# Analog_Sensors.net
KiCad netlist of a schematic drawn in Altium Designer
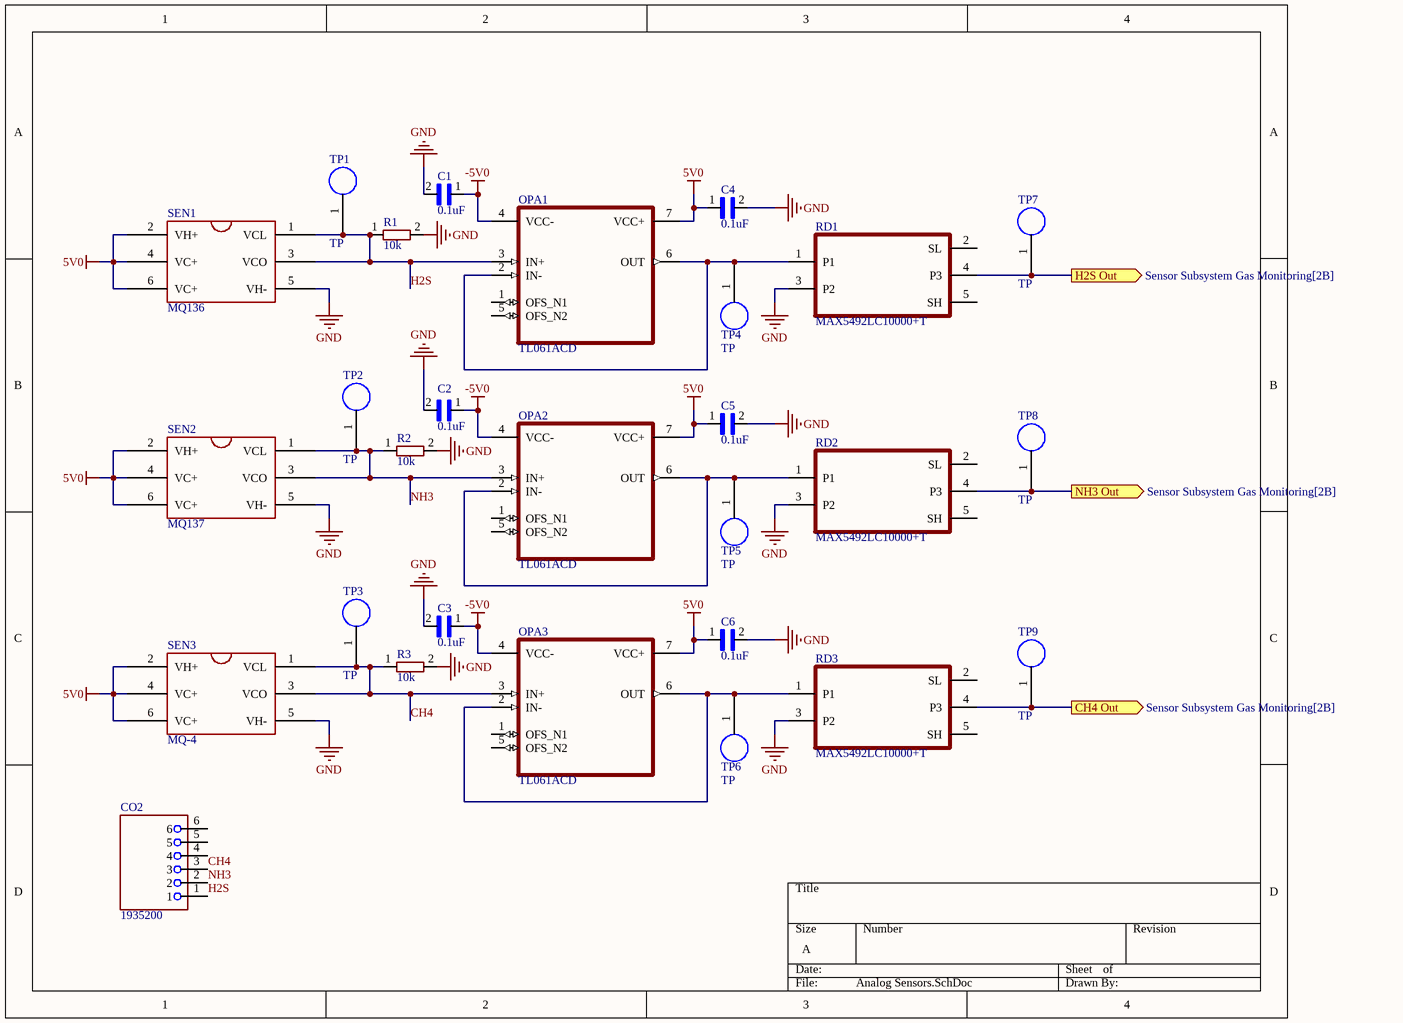
[diagram p0: Analog Sensors.SchDoc]

(export (version "E")
  (design (tool "Eeschema 10.0.6"))
  (components
    (comp (ref "C1")
      (value "0.1uF")
      (footprint "0.1uF Capacitor")
      (description "No Description Available")
      (libsource (lib "0.1uF Capacitor") (part "CC1206JRX7R9BB104"))
    )
    (comp (ref "C2")
      (value "0.1uF")
      (footprint "0.1uF Capacitor")
      (description "No Description Available")
      (libsource (lib "0.1uF Capacitor") (part "CC1206JRX7R9BB104"))
    )
    (comp (ref "C3")
      (value "0.1uF")
      (footprint "0.1uF Capacitor")
      (description "No Description Available")
      (libsource (lib "0.1uF Capacitor") (part "CC1206JRX7R9BB104"))
    )
    (comp (ref "C4")
      (value "0.1uF")
      (footprint "0.1uF Capacitor")
      (description "No Description Available")
      (libsource (lib "") (part "CC1206JRX7R9BB104_1"))
    )
    (comp (ref "C5")
      (value "0.1uF")
      (footprint "0.1uF Capacitor")
      (description "No Description Available")
      (libsource (lib "") (part "CC1206JRX7R9BB104_1"))
    )
    (comp (ref "C6")
      (value "0.1uF")
      (footprint "0.1uF Capacitor")
      (description "No Description Available")
      (libsource (lib "") (part "CC1206JRX7R9BB104_1"))
    )
    (comp (ref "CO2")
      (value "1935200")
      (footprint "PHOENIX_1935200")
      (fields (field (name "MF") "Littelfuse"))
      (libsource (lib "Main Connector") (part "1935200"))
    )
    (comp (ref "OPA1")
      (value "TL061ACD")
      (footprint "TL061ACD:SOIC127P599X175-8N")
      (libsource (lib "TL061ACD") (part "TL061ACD"))
    )
    (comp (ref "OPA2")
      (value "TL061ACD")
      (footprint "TL061ACD:SOIC127P599X175-8N")
      (libsource (lib "TL061ACD") (part "TL061ACD"))
    )
    (comp (ref "OPA3")
      (value "TL061ACD")
      (footprint "TL061ACD:SOIC127P599X175-8N")
      (libsource (lib "TL061ACD") (part "TL061ACD"))
    )
    (comp (ref "R1")
      (value "10k")
      (footprint "10K Resistor:0603")
      (description "http://octopart.com/rc0603fr-1310kl-yageo+%2F+phycomp-25905087")
      (fields (field (name "MP") "RC0603FR-1310KL"))
      (libsource (lib "10K Resistor") (part "RC0603FR-1310KL"))
    )
    (comp (ref "R2")
      (value "10k")
      (footprint "10K Resistor:0603")
      (description "http://octopart.com/rc0603fr-1310kl-yageo+%2F+phycomp-25905087")
      (fields (field (name "MP") "RC0603FR-1310KL"))
      (libsource (lib "10K Resistor") (part "RC0603FR-1310KL"))
    )
    (comp (ref "R3")
      (value "10k")
      (footprint "10K Resistor:0603")
      (description "http://octopart.com/rc0603fr-1310kl-yageo+%2F+phycomp-25905087")
      (fields (field (name "MP") "RC0603FR-1310KL"))
      (libsource (lib "10K Resistor") (part "RC0603FR-1310KL"))
    )
    (comp (ref "RD1")
      (value "MAX5492LC10000+T")
      (footprint "SOT95P280X145-5N")
      (description "Res NET 9.09K Ohm/910 Ohm 0.1% 0.5714W Â±35ppm/Â°C VOLT/D 5-Pin SOT-23 Gull Wing SMD T/R")
      (fields (field (name "MF") "Maxim Integrated Products"))
      (libsource (lib "Voltage Divider") (part "MAX5492LC10000+T"))
    )
    (comp (ref "RD2")
      (value "MAX5492LC10000+T")
      (footprint "SOT95P280X145-5N")
      (description "Res NET 9.09K Ohm/910 Ohm 0.1% 0.5714W Â±35ppm/Â°C VOLT/D 5-Pin SOT-23 Gull Wing SMD T/R")
      (fields (field (name "MF") "Maxim Integrated Products"))
      (libsource (lib "Voltage Divider") (part "MAX5492LC10000+T"))
    )
    (comp (ref "RD3")
      (value "MAX5492LC10000+T")
      (footprint "SOT95P280X145-5N")
      (description "Res NET 9.09K Ohm/910 Ohm 0.1% 0.5714W Â±35ppm/Â°C VOLT/D 5-Pin SOT-23 Gull Wing SMD T/R")
      (fields (field (name "MF") "Maxim Integrated Products"))
      (libsource (lib "Voltage Divider") (part "MAX5492LC10000+T"))
    )
    (comp (ref "SEN1")
      (value "MQ136")
      (footprint "MQ136")
      (description "Hydrogen Sulfide Sensor")
      (libsource (lib "MQ136") (part "MQ136"))
    )
    (comp (ref "SEN2")
      (value "MQ137")
      (footprint "MQ137")
      (description "Ammonia Sensor")
      (libsource (lib "MQ137") (part "MQ137"))
    )
    (comp (ref "SEN3")
      (value "MQ-4")
      (footprint "MQ4")
      (description "Methane Sensor")
      (libsource (lib "MQ-4") (part "MQ-4"))
    )
    (comp (ref "TP1")
      (value "TP")
      (footprint "TestPoint")
      (description "Test point for voltage, current, ect.")
      (libsource (lib "TestPoint") (part "TestPoint"))
    )
    (comp (ref "TP2")
      (value "TP")
      (footprint "TestPoint")
      (description "Test point for voltage, current, ect.")
      (libsource (lib "TestPoint") (part "TestPoint"))
    )
    (comp (ref "TP3")
      (value "TP")
      (footprint "TestPoint")
      (description "Test point for voltage, current, ect.")
      (libsource (lib "TestPoint") (part "TestPoint"))
    )
    (comp (ref "TP4")
      (value "TP")
      (footprint "TestPoint")
      (description "Test point for voltage, current, ect.")
      (libsource (lib "TestPoint") (part "TestPoint"))
    )
    (comp (ref "TP5")
      (value "TP")
      (footprint "TestPoint")
      (description "Test point for voltage, current, ect.")
      (libsource (lib "TestPoint") (part "TestPoint"))
    )
    (comp (ref "TP6")
      (value "TP")
      (footprint "TestPoint")
      (description "Test point for voltage, current, ect.")
      (libsource (lib "TestPoint") (part "TestPoint"))
    )
    (comp (ref "TP7")
      (value "TP")
      (footprint "TestPoint")
      (description "Test point for voltage, current, ect.")
      (libsource (lib "TestPoint") (part "TestPoint"))
    )
    (comp (ref "TP8")
      (value "TP")
      (footprint "TestPoint")
      (description "Test point for voltage, current, ect.")
      (libsource (lib "TestPoint") (part "TestPoint"))
    )
    (comp (ref "TP9")
      (value "TP")
      (footprint "TestPoint")
      (description "Test point for voltage, current, ect.")
      (libsource (lib "TestPoint") (part "TestPoint"))
    )
  )
  (nets
    (net (code "1") (name "-5V0") (class "Default")
      (node (ref "C1") (pin "1") (pintype "passive"))
      (node (ref "C2") (pin "1") (pintype "passive"))
      (node (ref "C3") (pin "1") (pintype "passive"))
      (node (ref "OPA1") (pin "4") (pinfunction "VCC-_4") (pintype "power_in"))
      (node (ref "OPA2") (pin "4") (pinfunction "VCC-_4") (pintype "power_in"))
      (node (ref "OPA3") (pin "4") (pinfunction "VCC-_4") (pintype "power_in"))
    )
    (net (code "2") (name "/CH4") (class "Default")
      (node (ref "CO2") (pin "3") (pinfunction "3_3") (pintype "passive"))
      (node (ref "OPA3") (pin "3") (pinfunction "IN+_3") (pintype "input"))
      (node (ref "R3") (pin "1") (pintype "passive"))
      (node (ref "SEN3") (pin "1") (pinfunction "VCL_1") (pintype "passive"))
      (node (ref "SEN3") (pin "3") (pinfunction "VCO_3") (pintype "passive"))
      (node (ref "TP3") (pin "1") (pintype "passive"))
    )
    (net (code "3") (name "/CH4 Out") (class "Default")
      (node (ref "RD3") (pin "4") (pinfunction "P3_4") (pintype "passive"))
      (node (ref "TP9") (pin "1") (pintype "passive"))
    )
    (net (code "4") (name "/H2S") (class "Default")
      (node (ref "CO2") (pin "1") (pinfunction "1_1") (pintype "passive"))
      (node (ref "OPA1") (pin "3") (pinfunction "IN+_3") (pintype "input"))
      (node (ref "R1") (pin "1") (pintype "passive"))
      (node (ref "SEN1") (pin "1") (pinfunction "VCL_1") (pintype "passive"))
      (node (ref "SEN1") (pin "3") (pinfunction "VCO_3") (pintype "passive"))
      (node (ref "TP1") (pin "1") (pintype "passive"))
    )
    (net (code "5") (name "/H2S Out") (class "Default")
      (node (ref "RD1") (pin "4") (pinfunction "P3_4") (pintype "passive"))
      (node (ref "TP7") (pin "1") (pintype "passive"))
    )
    (net (code "6") (name "/NH3") (class "Default")
      (node (ref "CO2") (pin "2") (pinfunction "2_2") (pintype "passive"))
      (node (ref "OPA2") (pin "3") (pinfunction "IN+_3") (pintype "input"))
      (node (ref "R2") (pin "1") (pintype "passive"))
      (node (ref "SEN2") (pin "1") (pinfunction "VCL_1") (pintype "passive"))
      (node (ref "SEN2") (pin "3") (pinfunction "VCO_3") (pintype "passive"))
      (node (ref "TP2") (pin "1") (pintype "passive"))
    )
    (net (code "7") (name "/NH3 Out") (class "Default")
      (node (ref "RD2") (pin "4") (pinfunction "P3_4") (pintype "passive"))
      (node (ref "TP8") (pin "1") (pintype "passive"))
    )
    (net (code "8") (name "5V0") (class "Default")
      (node (ref "C4") (pin "1") (pintype "passive"))
      (node (ref "C5") (pin "1") (pintype "passive"))
      (node (ref "C6") (pin "1") (pintype "passive"))
      (node (ref "OPA1") (pin "7") (pinfunction "VCC+_7") (pintype "power_in"))
      (node (ref "OPA2") (pin "7") (pinfunction "VCC+_7") (pintype "power_in"))
      (node (ref "OPA3") (pin "7") (pinfunction "VCC+_7") (pintype "power_in"))
      (node (ref "SEN1") (pin "2") (pinfunction "VH+_2") (pintype "passive"))
      (node (ref "SEN1") (pin "4") (pinfunction "VC+_4") (pintype "passive"))
      (node (ref "SEN1") (pin "6") (pinfunction "VC+_6") (pintype "passive"))
      (node (ref "SEN2") (pin "2") (pinfunction "VH+_2") (pintype "passive"))
      (node (ref "SEN2") (pin "4") (pinfunction "VC+_4") (pintype "passive"))
      (node (ref "SEN2") (pin "6") (pinfunction "VC+_6") (pintype "passive"))
      (node (ref "SEN3") (pin "2") (pinfunction "VH+_2") (pintype "passive"))
      (node (ref "SEN3") (pin "4") (pinfunction "VC+_4") (pintype "passive"))
      (node (ref "SEN3") (pin "6") (pinfunction "VC+_6") (pintype "passive"))
    )
    (net (code "9") (name "GND") (class "Default")
      (node (ref "C1") (pin "2") (pintype "passive"))
      (node (ref "C2") (pin "2") (pintype "passive"))
      (node (ref "C3") (pin "2") (pintype "passive"))
      (node (ref "C4") (pin "2") (pintype "passive"))
      (node (ref "C5") (pin "2") (pintype "passive"))
      (node (ref "C6") (pin "2") (pintype "passive"))
      (node (ref "R1") (pin "2") (pintype "passive"))
      (node (ref "R2") (pin "2") (pintype "passive"))
      (node (ref "R3") (pin "2") (pintype "passive"))
      (node (ref "RD1") (pin "3") (pinfunction "P2_3") (pintype "passive"))
      (node (ref "RD2") (pin "3") (pinfunction "P2_3") (pintype "passive"))
      (node (ref "RD3") (pin "3") (pinfunction "P2_3") (pintype "passive"))
      (node (ref "SEN1") (pin "5") (pinfunction "VH-_5") (pintype "passive"))
      (node (ref "SEN2") (pin "5") (pinfunction "VH-_5") (pintype "passive"))
      (node (ref "SEN3") (pin "5") (pinfunction "VH-_5") (pintype "passive"))
    )
    (net (code "10") (name "Net-(OPA1-IN-)") (class "Default")
      (node (ref "OPA1") (pin "2") (pinfunction "IN-_2") (pintype "input"))
      (node (ref "OPA1") (pin "6") (pinfunction "OUT_6") (pintype "output"))
      (node (ref "RD1") (pin "1") (pinfunction "P1_1") (pintype "passive"))
      (node (ref "TP4") (pin "1") (pintype "passive"))
    )
    (net (code "11") (name "Net-(OPA2-IN-)") (class "Default")
      (node (ref "OPA2") (pin "2") (pinfunction "IN-_2") (pintype "input"))
      (node (ref "OPA2") (pin "6") (pinfunction "OUT_6") (pintype "output"))
      (node (ref "RD2") (pin "1") (pinfunction "P1_1") (pintype "passive"))
      (node (ref "TP5") (pin "1") (pintype "passive"))
    )
    (net (code "12") (name "Net-(OPA3-IN-)") (class "Default")
      (node (ref "OPA3") (pin "2") (pinfunction "IN-_2") (pintype "input"))
      (node (ref "OPA3") (pin "6") (pinfunction "OUT_6") (pintype "output"))
      (node (ref "RD3") (pin "1") (pinfunction "P1_1") (pintype "passive"))
      (node (ref "TP6") (pin "1") (pintype "passive"))
    )
    (net (code "13") (name "unconnected-(CO2-Pad4)") (class "Default")
      (node (ref "CO2") (pin "4") (pinfunction "4_4") (pintype "passive"))
    )
    (net (code "14") (name "unconnected-(CO2-Pad5)") (class "Default")
      (node (ref "CO2") (pin "5") (pinfunction "5_5") (pintype "passive"))
    )
    (net (code "15") (name "unconnected-(CO2-Pad6)") (class "Default")
      (node (ref "CO2") (pin "6") (pinfunction "6_6") (pintype "passive"))
    )
    (net (code "16") (name "unconnected-(OPA1-OFS_N1-Pad1)") (class "Default")
      (node (ref "OPA1") (pin "1") (pinfunction "OFS_N1_1") (pintype "bidirectional"))
    )
    (net (code "17") (name "unconnected-(OPA1-OFS_N2-Pad5)") (class "Default")
      (node (ref "OPA1") (pin "5") (pinfunction "OFS_N2_5") (pintype "bidirectional"))
    )
    (net (code "18") (name "unconnected-(OPA2-OFS_N1-Pad1)") (class "Default")
      (node (ref "OPA2") (pin "1") (pinfunction "OFS_N1_1") (pintype "bidirectional"))
    )
    (net (code "19") (name "unconnected-(OPA2-OFS_N2-Pad5)") (class "Default")
      (node (ref "OPA2") (pin "5") (pinfunction "OFS_N2_5") (pintype "bidirectional"))
    )
    (net (code "20") (name "unconnected-(OPA3-OFS_N1-Pad1)") (class "Default")
      (node (ref "OPA3") (pin "1") (pinfunction "OFS_N1_1") (pintype "bidirectional"))
    )
    (net (code "21") (name "unconnected-(OPA3-OFS_N2-Pad5)") (class "Default")
      (node (ref "OPA3") (pin "5") (pinfunction "OFS_N2_5") (pintype "bidirectional"))
    )
    (net (code "22") (name "unconnected-(RD1-SH-Pad5)") (class "Default")
      (node (ref "RD1") (pin "5") (pinfunction "SH_5") (pintype "passive"))
    )
    (net (code "23") (name "unconnected-(RD1-SL-Pad2)") (class "Default")
      (node (ref "RD1") (pin "2") (pinfunction "SL_2") (pintype "passive"))
    )
    (net (code "24") (name "unconnected-(RD2-SH-Pad5)") (class "Default")
      (node (ref "RD2") (pin "5") (pinfunction "SH_5") (pintype "passive"))
    )
    (net (code "25") (name "unconnected-(RD2-SL-Pad2)") (class "Default")
      (node (ref "RD2") (pin "2") (pinfunction "SL_2") (pintype "passive"))
    )
    (net (code "26") (name "unconnected-(RD3-SH-Pad5)") (class "Default")
      (node (ref "RD3") (pin "5") (pinfunction "SH_5") (pintype "passive"))
    )
    (net (code "27") (name "unconnected-(RD3-SL-Pad2)") (class "Default")
      (node (ref "RD3") (pin "2") (pinfunction "SL_2") (pintype "passive"))
    )
  )
)
